# denziben.net
KiCad netlist of a schematic drawn in EAGLE
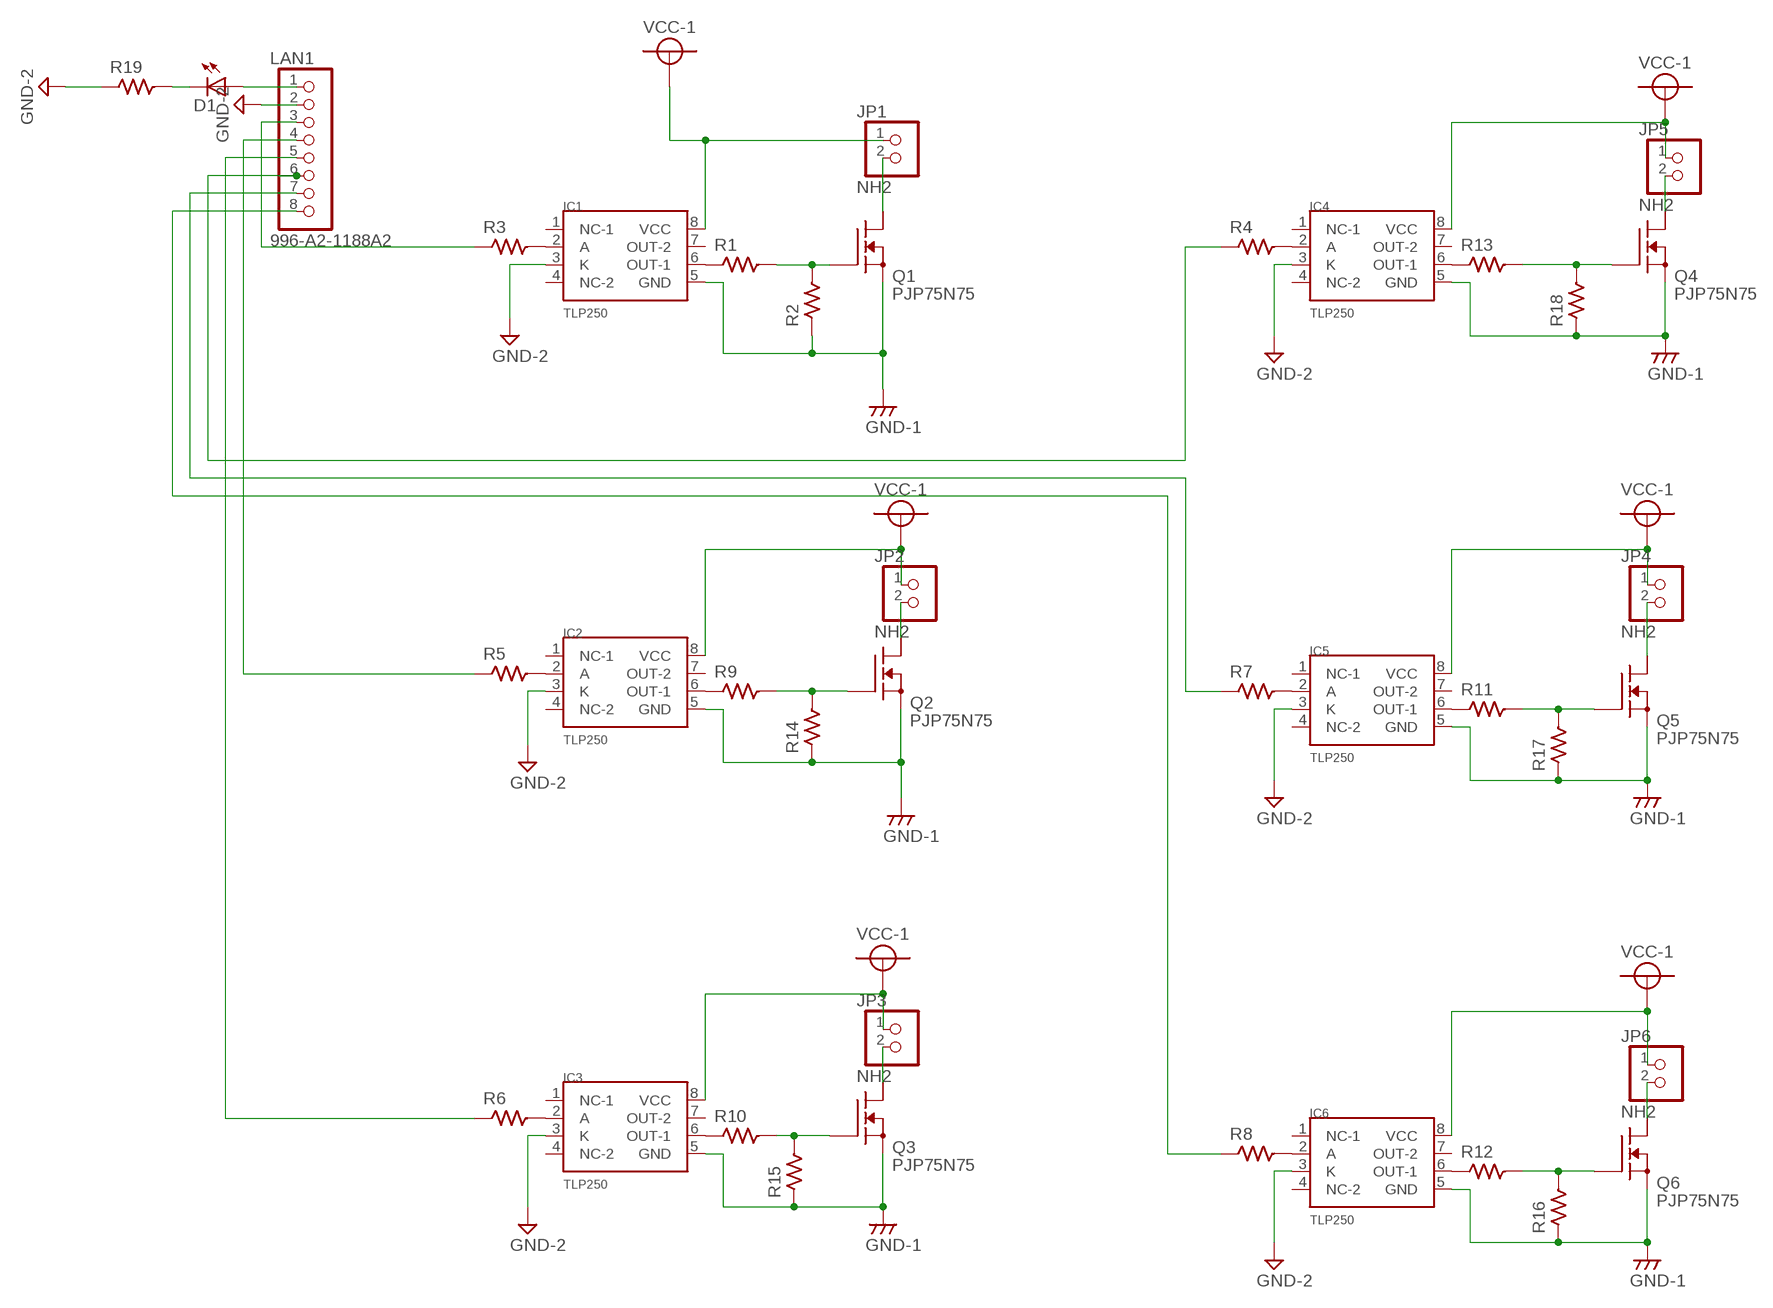
[diagram p0: schematic, sheet 1]

(export (version "E")
  (design (tool "Eeschema 10.0.6"))
  (components
    (comp (ref "D1")
      (value "LED\"\"")
      (footprint "eagle-import:LED5MM")
      (libsource (lib "eagle-import") (part "LED{dblquote}{dblquote}"))
    )
    (comp (ref "IC1")
      (value "TLP250")
      (footprint "eagle-import:DIL8")
      (libsource (lib "eagle-import") (part "TLP250"))
    )
    (comp (ref "IC2")
      (value "TLP250")
      (footprint "eagle-import:DIL8")
      (libsource (lib "eagle-import") (part "TLP250"))
    )
    (comp (ref "IC3")
      (value "TLP250")
      (footprint "eagle-import:DIL8")
      (libsource (lib "eagle-import") (part "TLP250"))
    )
    (comp (ref "IC4")
      (value "TLP250")
      (footprint "eagle-import:DIL8")
      (libsource (lib "eagle-import") (part "TLP250"))
    )
    (comp (ref "IC5")
      (value "TLP250")
      (footprint "eagle-import:DIL8")
      (libsource (lib "eagle-import") (part "TLP250"))
    )
    (comp (ref "IC6")
      (value "TLP250")
      (footprint "eagle-import:DIL8")
      (libsource (lib "eagle-import") (part "TLP250"))
    )
    (comp (ref "JP1")
      (value "NH2")
      (footprint "eagle-import:NH2")
      (libsource (lib "eagle-import") (part "NH2"))
    )
    (comp (ref "JP2")
      (value "NH2")
      (footprint "eagle-import:NH2")
      (libsource (lib "eagle-import") (part "NH2"))
    )
    (comp (ref "JP3")
      (value "NH2")
      (footprint "eagle-import:NH2")
      (libsource (lib "eagle-import") (part "NH2"))
    )
    (comp (ref "JP4")
      (value "NH2")
      (footprint "eagle-import:NH2")
      (libsource (lib "eagle-import") (part "NH2"))
    )
    (comp (ref "JP5")
      (value "NH2")
      (footprint "eagle-import:NH2")
      (libsource (lib "eagle-import") (part "NH2"))
    )
    (comp (ref "JP6")
      (value "NH2")
      (footprint "eagle-import:NH2")
      (libsource (lib "eagle-import") (part "NH2"))
    )
    (comp (ref "LAN1")
      (value "996-A2-1188A2")
      (footprint "eagle-import:996-A2-1188A2")
      (libsource (lib "eagle-import") (part "996-A2-1188A2"))
    )
    (comp (ref "Q1")
      (value "PJP75N75")
      (footprint "eagle-import:TO220")
      (libsource (lib "eagle-import") (part "PJP75N75"))
    )
    (comp (ref "Q2")
      (value "PJP75N75")
      (footprint "eagle-import:TO220")
      (libsource (lib "eagle-import") (part "PJP75N75"))
    )
    (comp (ref "Q3")
      (value "PJP75N75")
      (footprint "eagle-import:TO220")
      (libsource (lib "eagle-import") (part "PJP75N75"))
    )
    (comp (ref "Q4")
      (value "PJP75N75")
      (footprint "eagle-import:TO220")
      (libsource (lib "eagle-import") (part "PJP75N75"))
    )
    (comp (ref "Q5")
      (value "PJP75N75")
      (footprint "eagle-import:TO220")
      (libsource (lib "eagle-import") (part "PJP75N75"))
    )
    (comp (ref "Q6")
      (value "PJP75N75")
      (footprint "eagle-import:TO220")
      (libsource (lib "eagle-import") (part "PJP75N75"))
    )
    (comp (ref "R1")
      (value "R1/4W")
      (footprint "eagle-import:R_1_4W")
      (libsource (lib "eagle-import") (part "R1/4W"))
    )
    (comp (ref "R2")
      (value "R1/4W")
      (footprint "eagle-import:R_1_4W")
      (libsource (lib "eagle-import") (part "R1/4W"))
    )
    (comp (ref "R3")
      (value "R1/4W")
      (footprint "eagle-import:R_1_4W")
      (libsource (lib "eagle-import") (part "R1/4W"))
    )
    (comp (ref "R4")
      (value "R1/4W")
      (footprint "eagle-import:R_1_4W")
      (libsource (lib "eagle-import") (part "R1/4W"))
    )
    (comp (ref "R5")
      (value "R1/4W")
      (footprint "eagle-import:R_1_4W")
      (libsource (lib "eagle-import") (part "R1/4W"))
    )
    (comp (ref "R6")
      (value "R1/4W")
      (footprint "eagle-import:R_1_4W")
      (libsource (lib "eagle-import") (part "R1/4W"))
    )
    (comp (ref "R7")
      (value "R1/4W")
      (footprint "eagle-import:R_1_4W")
      (libsource (lib "eagle-import") (part "R1/4W"))
    )
    (comp (ref "R8")
      (value "R1/4W")
      (footprint "eagle-import:R_1_4W")
      (libsource (lib "eagle-import") (part "R1/4W"))
    )
    (comp (ref "R9")
      (value "R1/4W")
      (footprint "eagle-import:R_1_4W")
      (libsource (lib "eagle-import") (part "R1/4W"))
    )
    (comp (ref "R10")
      (value "R1/4W")
      (footprint "eagle-import:R_1_4W")
      (libsource (lib "eagle-import") (part "R1/4W"))
    )
    (comp (ref "R11")
      (value "R1/4W")
      (footprint "eagle-import:R_1_4W")
      (libsource (lib "eagle-import") (part "R1/4W"))
    )
    (comp (ref "R12")
      (value "R1/4W")
      (footprint "eagle-import:R_1_4W")
      (libsource (lib "eagle-import") (part "R1/4W"))
    )
    (comp (ref "R13")
      (value "R1/4W")
      (footprint "eagle-import:R_1_4W")
      (libsource (lib "eagle-import") (part "R1/4W"))
    )
    (comp (ref "R14")
      (value "R1/4W")
      (footprint "eagle-import:R_1_4W")
      (libsource (lib "eagle-import") (part "R1/4W"))
    )
    (comp (ref "R15")
      (value "R1/4W")
      (footprint "eagle-import:R_1_4W")
      (libsource (lib "eagle-import") (part "R1/4W"))
    )
    (comp (ref "R16")
      (value "R1/4W")
      (footprint "eagle-import:R_1_4W")
      (libsource (lib "eagle-import") (part "R1/4W"))
    )
    (comp (ref "R17")
      (value "R1/4W")
      (footprint "eagle-import:R_1_4W")
      (libsource (lib "eagle-import") (part "R1/4W"))
    )
    (comp (ref "R18")
      (value "R1/4W")
      (footprint "eagle-import:R_1_4W")
      (libsource (lib "eagle-import") (part "R1/4W"))
    )
    (comp (ref "R19")
      (value "R1/4W")
      (footprint "eagle-import:R_1_4W")
      (libsource (lib "eagle-import") (part "R1/4W"))
    )
  )
  (nets
    (net (code "1") (name "GND-1") (class "Default")
      (node (ref "IC1") (pin "5") (pinfunction "GND_5") (pintype "bidirectional"))
      (node (ref "IC2") (pin "5") (pinfunction "GND_5") (pintype "bidirectional"))
      (node (ref "IC3") (pin "5") (pinfunction "GND_5") (pintype "bidirectional"))
      (node (ref "IC4") (pin "5") (pinfunction "GND_5") (pintype "bidirectional"))
      (node (ref "IC5") (pin "5") (pinfunction "GND_5") (pintype "bidirectional"))
      (node (ref "IC6") (pin "5") (pinfunction "GND_5") (pintype "bidirectional"))
      (node (ref "Q1") (pin "3") (pinfunction "NｃｈS_3") (pintype "passive"))
      (node (ref "Q2") (pin "3") (pinfunction "NｃｈS_3") (pintype "passive"))
      (node (ref "Q3") (pin "3") (pinfunction "NｃｈS_3") (pintype "passive"))
      (node (ref "Q4") (pin "3") (pinfunction "NｃｈS_3") (pintype "passive"))
      (node (ref "Q5") (pin "3") (pinfunction "NｃｈS_3") (pintype "passive"))
      (node (ref "Q6") (pin "3") (pinfunction "NｃｈS_3") (pintype "passive"))
      (node (ref "R14") (pin "P$1") (pinfunction "P$1_P$1") (pintype "passive"))
      (node (ref "R15") (pin "P$1") (pinfunction "P$1_P$1") (pintype "passive"))
      (node (ref "R16") (pin "P$1") (pinfunction "P$1_P$1") (pintype "passive"))
      (node (ref "R17") (pin "P$1") (pinfunction "P$1_P$1") (pintype "passive"))
      (node (ref "R18") (pin "P$1") (pinfunction "P$1_P$1") (pintype "passive"))
      (node (ref "R2") (pin "P$1") (pinfunction "P$1_P$1") (pintype "passive"))
    )
    (net (code "2") (name "GND-2") (class "Default")
      (node (ref "IC1") (pin "3") (pinfunction "K_3") (pintype "bidirectional"))
      (node (ref "IC2") (pin "3") (pinfunction "K_3") (pintype "bidirectional"))
      (node (ref "IC3") (pin "3") (pinfunction "K_3") (pintype "bidirectional"))
      (node (ref "IC4") (pin "3") (pinfunction "K_3") (pintype "bidirectional"))
      (node (ref "IC5") (pin "3") (pinfunction "K_3") (pintype "bidirectional"))
      (node (ref "IC6") (pin "3") (pinfunction "K_3") (pintype "bidirectional"))
      (node (ref "LAN1") (pin "2") (pinfunction "P$2_2") (pintype "bidirectional"))
      (node (ref "R19") (pin "P$1") (pinfunction "P$1_P$1") (pintype "passive"))
    )
    (net (code "3") (name "Net-(D1-C)") (class "Default")
      (node (ref "D1") (pin "K") (pinfunction "C_K") (pintype "passive"))
      (node (ref "R19") (pin "P$2") (pinfunction "P$2_P$2") (pintype "passive"))
    )
    (net (code "4") (name "Net-(IC1-A)") (class "Default")
      (node (ref "IC1") (pin "2") (pinfunction "A_2") (pintype "bidirectional"))
      (node (ref "R3") (pin "P$2") (pinfunction "P$2_P$2") (pintype "passive"))
    )
    (net (code "5") (name "Net-(IC1-OUT-1)") (class "Default")
      (node (ref "IC1") (pin "6") (pinfunction "OUT-1_6") (pintype "bidirectional"))
      (node (ref "R1") (pin "P$1") (pinfunction "P$1_P$1") (pintype "passive"))
    )
    (net (code "6") (name "Net-(IC2-A)") (class "Default")
      (node (ref "IC2") (pin "2") (pinfunction "A_2") (pintype "bidirectional"))
      (node (ref "R5") (pin "P$2") (pinfunction "P$2_P$2") (pintype "passive"))
    )
    (net (code "7") (name "Net-(IC2-OUT-1)") (class "Default")
      (node (ref "IC2") (pin "6") (pinfunction "OUT-1_6") (pintype "bidirectional"))
      (node (ref "R9") (pin "P$1") (pinfunction "P$1_P$1") (pintype "passive"))
    )
    (net (code "8") (name "Net-(IC3-A)") (class "Default")
      (node (ref "IC3") (pin "2") (pinfunction "A_2") (pintype "bidirectional"))
      (node (ref "R6") (pin "P$2") (pinfunction "P$2_P$2") (pintype "passive"))
    )
    (net (code "9") (name "Net-(IC3-OUT-1)") (class "Default")
      (node (ref "IC3") (pin "6") (pinfunction "OUT-1_6") (pintype "bidirectional"))
      (node (ref "R10") (pin "P$1") (pinfunction "P$1_P$1") (pintype "passive"))
    )
    (net (code "10") (name "Net-(IC4-A)") (class "Default")
      (node (ref "IC4") (pin "2") (pinfunction "A_2") (pintype "bidirectional"))
      (node (ref "R4") (pin "P$2") (pinfunction "P$2_P$2") (pintype "passive"))
    )
    (net (code "11") (name "Net-(IC4-OUT-1)") (class "Default")
      (node (ref "IC4") (pin "6") (pinfunction "OUT-1_6") (pintype "bidirectional"))
      (node (ref "R13") (pin "P$1") (pinfunction "P$1_P$1") (pintype "passive"))
    )
    (net (code "12") (name "Net-(IC5-A)") (class "Default")
      (node (ref "IC5") (pin "2") (pinfunction "A_2") (pintype "bidirectional"))
      (node (ref "R7") (pin "P$2") (pinfunction "P$2_P$2") (pintype "passive"))
    )
    (net (code "13") (name "Net-(IC5-OUT-1)") (class "Default")
      (node (ref "IC5") (pin "6") (pinfunction "OUT-1_6") (pintype "bidirectional"))
      (node (ref "R11") (pin "P$1") (pinfunction "P$1_P$1") (pintype "passive"))
    )
    (net (code "14") (name "Net-(IC6-A)") (class "Default")
      (node (ref "IC6") (pin "2") (pinfunction "A_2") (pintype "bidirectional"))
      (node (ref "R8") (pin "P$2") (pinfunction "P$2_P$2") (pintype "passive"))
    )
    (net (code "15") (name "Net-(IC6-OUT-1)") (class "Default")
      (node (ref "IC6") (pin "6") (pinfunction "OUT-1_6") (pintype "bidirectional"))
      (node (ref "R12") (pin "P$1") (pinfunction "P$1_P$1") (pintype "passive"))
    )
    (net (code "16") (name "Net-(JP1-P$2)") (class "Default")
      (node (ref "JP1") (pin "2") (pinfunction "P$2_2") (pintype "bidirectional"))
      (node (ref "Q1") (pin "2") (pinfunction "NｃｈD_2") (pintype "passive"))
    )
    (net (code "17") (name "Net-(JP2-P$2)") (class "Default")
      (node (ref "JP2") (pin "2") (pinfunction "P$2_2") (pintype "bidirectional"))
      (node (ref "Q2") (pin "2") (pinfunction "NｃｈD_2") (pintype "passive"))
    )
    (net (code "18") (name "Net-(JP3-P$2)") (class "Default")
      (node (ref "JP3") (pin "2") (pinfunction "P$2_2") (pintype "bidirectional"))
      (node (ref "Q3") (pin "2") (pinfunction "NｃｈD_2") (pintype "passive"))
    )
    (net (code "19") (name "Net-(JP4-P$2)") (class "Default")
      (node (ref "JP4") (pin "2") (pinfunction "P$2_2") (pintype "bidirectional"))
      (node (ref "Q5") (pin "2") (pinfunction "NｃｈD_2") (pintype "passive"))
    )
    (net (code "20") (name "Net-(JP5-P$2)") (class "Default")
      (node (ref "JP5") (pin "2") (pinfunction "P$2_2") (pintype "bidirectional"))
      (node (ref "Q4") (pin "2") (pinfunction "NｃｈD_2") (pintype "passive"))
    )
    (net (code "21") (name "Net-(JP6-P$2)") (class "Default")
      (node (ref "JP6") (pin "2") (pinfunction "P$2_2") (pintype "bidirectional"))
      (node (ref "Q6") (pin "2") (pinfunction "NｃｈD_2") (pintype "passive"))
    )
    (net (code "22") (name "Net-(LAN1-P$1)") (class "Default")
      (node (ref "D1") (pin "A") (pinfunction "A_A") (pintype "passive"))
      (node (ref "LAN1") (pin "1") (pinfunction "P$1_1") (pintype "bidirectional"))
    )
    (net (code "23") (name "Net-(LAN1-P$3)") (class "Default")
      (node (ref "LAN1") (pin "3") (pinfunction "P$3_3") (pintype "bidirectional"))
      (node (ref "R3") (pin "P$1") (pinfunction "P$1_P$1") (pintype "passive"))
    )
    (net (code "24") (name "Net-(LAN1-P$4)") (class "Default")
      (node (ref "LAN1") (pin "4") (pinfunction "P$4_4") (pintype "bidirectional"))
      (node (ref "R5") (pin "P$1") (pinfunction "P$1_P$1") (pintype "passive"))
    )
    (net (code "25") (name "Net-(LAN1-P$5)") (class "Default")
      (node (ref "LAN1") (pin "5") (pinfunction "P$5_5") (pintype "bidirectional"))
      (node (ref "R6") (pin "P$1") (pinfunction "P$1_P$1") (pintype "passive"))
    )
    (net (code "26") (name "Net-(LAN1-P$6)") (class "Default")
      (node (ref "LAN1") (pin "6") (pinfunction "P$6_6") (pintype "bidirectional"))
      (node (ref "R4") (pin "P$1") (pinfunction "P$1_P$1") (pintype "passive"))
    )
    (net (code "27") (name "Net-(LAN1-P$7)") (class "Default")
      (node (ref "LAN1") (pin "7") (pinfunction "P$7_7") (pintype "bidirectional"))
      (node (ref "R7") (pin "P$1") (pinfunction "P$1_P$1") (pintype "passive"))
    )
    (net (code "28") (name "Net-(LAN1-P$8)") (class "Default")
      (node (ref "LAN1") (pin "8") (pinfunction "P$8_8") (pintype "bidirectional"))
      (node (ref "R8") (pin "P$1") (pinfunction "P$1_P$1") (pintype "passive"))
    )
    (net (code "29") (name "Net-(Q1-Nｃｈ-G)") (class "Default")
      (node (ref "Q1") (pin "1") (pinfunction "Nｃｈ-G_1") (pintype "passive"))
      (node (ref "R1") (pin "P$2") (pinfunction "P$2_P$2") (pintype "passive"))
      (node (ref "R2") (pin "P$2") (pinfunction "P$2_P$2") (pintype "passive"))
    )
    (net (code "30") (name "Net-(Q2-Nｃｈ-G)") (class "Default")
      (node (ref "Q2") (pin "1") (pinfunction "Nｃｈ-G_1") (pintype "passive"))
      (node (ref "R14") (pin "P$2") (pinfunction "P$2_P$2") (pintype "passive"))
      (node (ref "R9") (pin "P$2") (pinfunction "P$2_P$2") (pintype "passive"))
    )
    (net (code "31") (name "Net-(Q3-Nｃｈ-G)") (class "Default")
      (node (ref "Q3") (pin "1") (pinfunction "Nｃｈ-G_1") (pintype "passive"))
      (node (ref "R10") (pin "P$2") (pinfunction "P$2_P$2") (pintype "passive"))
      (node (ref "R15") (pin "P$2") (pinfunction "P$2_P$2") (pintype "passive"))
    )
    (net (code "32") (name "Net-(Q4-Nｃｈ-G)") (class "Default")
      (node (ref "Q4") (pin "1") (pinfunction "Nｃｈ-G_1") (pintype "passive"))
      (node (ref "R13") (pin "P$2") (pinfunction "P$2_P$2") (pintype "passive"))
      (node (ref "R18") (pin "P$2") (pinfunction "P$2_P$2") (pintype "passive"))
    )
    (net (code "33") (name "Net-(Q5-Nｃｈ-G)") (class "Default")
      (node (ref "Q5") (pin "1") (pinfunction "Nｃｈ-G_1") (pintype "passive"))
      (node (ref "R11") (pin "P$2") (pinfunction "P$2_P$2") (pintype "passive"))
      (node (ref "R17") (pin "P$2") (pinfunction "P$2_P$2") (pintype "passive"))
    )
    (net (code "34") (name "Net-(Q6-Nｃｈ-G)") (class "Default")
      (node (ref "Q6") (pin "1") (pinfunction "Nｃｈ-G_1") (pintype "passive"))
      (node (ref "R12") (pin "P$2") (pinfunction "P$2_P$2") (pintype "passive"))
      (node (ref "R16") (pin "P$2") (pinfunction "P$2_P$2") (pintype "passive"))
    )
    (net (code "35") (name "VCC-1") (class "Default")
      (node (ref "IC1") (pin "8") (pinfunction "VCC_8") (pintype "bidirectional"))
      (node (ref "IC2") (pin "8") (pinfunction "VCC_8") (pintype "bidirectional"))
      (node (ref "IC3") (pin "8") (pinfunction "VCC_8") (pintype "bidirectional"))
      (node (ref "IC4") (pin "8") (pinfunction "VCC_8") (pintype "bidirectional"))
      (node (ref "IC5") (pin "8") (pinfunction "VCC_8") (pintype "bidirectional"))
      (node (ref "IC6") (pin "8") (pinfunction "VCC_8") (pintype "bidirectional"))
      (node (ref "JP1") (pin "1") (pinfunction "P$1_1") (pintype "bidirectional"))
      (node (ref "JP2") (pin "1") (pinfunction "P$1_1") (pintype "bidirectional"))
      (node (ref "JP3") (pin "1") (pinfunction "P$1_1") (pintype "bidirectional"))
      (node (ref "JP4") (pin "1") (pinfunction "P$1_1") (pintype "bidirectional"))
      (node (ref "JP5") (pin "1") (pinfunction "P$1_1") (pintype "bidirectional"))
      (node (ref "JP6") (pin "1") (pinfunction "P$1_1") (pintype "bidirectional"))
    )
    (net (code "36") (name "unconnected-(IC1-NC-1-Pad1)") (class "Default")
      (node (ref "IC1") (pin "1") (pinfunction "NC-1_1") (pintype "bidirectional"))
    )
    (net (code "37") (name "unconnected-(IC1-NC-2-Pad4)") (class "Default")
      (node (ref "IC1") (pin "4") (pinfunction "NC-2_4") (pintype "bidirectional"))
    )
    (net (code "38") (name "unconnected-(IC1-OUT-2-Pad7)") (class "Default")
      (node (ref "IC1") (pin "7") (pinfunction "OUT-2_7") (pintype "bidirectional"))
    )
    (net (code "39") (name "unconnected-(IC2-NC-1-Pad1)") (class "Default")
      (node (ref "IC2") (pin "1") (pinfunction "NC-1_1") (pintype "bidirectional"))
    )
    (net (code "40") (name "unconnected-(IC2-NC-2-Pad4)") (class "Default")
      (node (ref "IC2") (pin "4") (pinfunction "NC-2_4") (pintype "bidirectional"))
    )
    (net (code "41") (name "unconnected-(IC2-OUT-2-Pad7)") (class "Default")
      (node (ref "IC2") (pin "7") (pinfunction "OUT-2_7") (pintype "bidirectional"))
    )
    (net (code "42") (name "unconnected-(IC3-NC-1-Pad1)") (class "Default")
      (node (ref "IC3") (pin "1") (pinfunction "NC-1_1") (pintype "bidirectional"))
    )
    (net (code "43") (name "unconnected-(IC3-NC-2-Pad4)") (class "Default")
      (node (ref "IC3") (pin "4") (pinfunction "NC-2_4") (pintype "bidirectional"))
    )
    (net (code "44") (name "unconnected-(IC3-OUT-2-Pad7)") (class "Default")
      (node (ref "IC3") (pin "7") (pinfunction "OUT-2_7") (pintype "bidirectional"))
    )
    (net (code "45") (name "unconnected-(IC4-NC-1-Pad1)") (class "Default")
      (node (ref "IC4") (pin "1") (pinfunction "NC-1_1") (pintype "bidirectional"))
    )
    (net (code "46") (name "unconnected-(IC4-NC-2-Pad4)") (class "Default")
      (node (ref "IC4") (pin "4") (pinfunction "NC-2_4") (pintype "bidirectional"))
    )
    (net (code "47") (name "unconnected-(IC4-OUT-2-Pad7)") (class "Default")
      (node (ref "IC4") (pin "7") (pinfunction "OUT-2_7") (pintype "bidirectional"))
    )
    (net (code "48") (name "unconnected-(IC5-NC-1-Pad1)") (class "Default")
      (node (ref "IC5") (pin "1") (pinfunction "NC-1_1") (pintype "bidirectional"))
    )
    (net (code "49") (name "unconnected-(IC5-NC-2-Pad4)") (class "Default")
      (node (ref "IC5") (pin "4") (pinfunction "NC-2_4") (pintype "bidirectional"))
    )
    (net (code "50") (name "unconnected-(IC5-OUT-2-Pad7)") (class "Default")
      (node (ref "IC5") (pin "7") (pinfunction "OUT-2_7") (pintype "bidirectional"))
    )
    (net (code "51") (name "unconnected-(IC6-NC-1-Pad1)") (class "Default")
      (node (ref "IC6") (pin "1") (pinfunction "NC-1_1") (pintype "bidirectional"))
    )
    (net (code "52") (name "unconnected-(IC6-NC-2-Pad4)") (class "Default")
      (node (ref "IC6") (pin "4") (pinfunction "NC-2_4") (pintype "bidirectional"))
    )
    (net (code "53") (name "unconnected-(IC6-OUT-2-Pad7)") (class "Default")
      (node (ref "IC6") (pin "7") (pinfunction "OUT-2_7") (pintype "bidirectional"))
    )
  )
)
